# PowerInput_Switch.net
KiCad netlist of a schematic drawn in Altium Designer
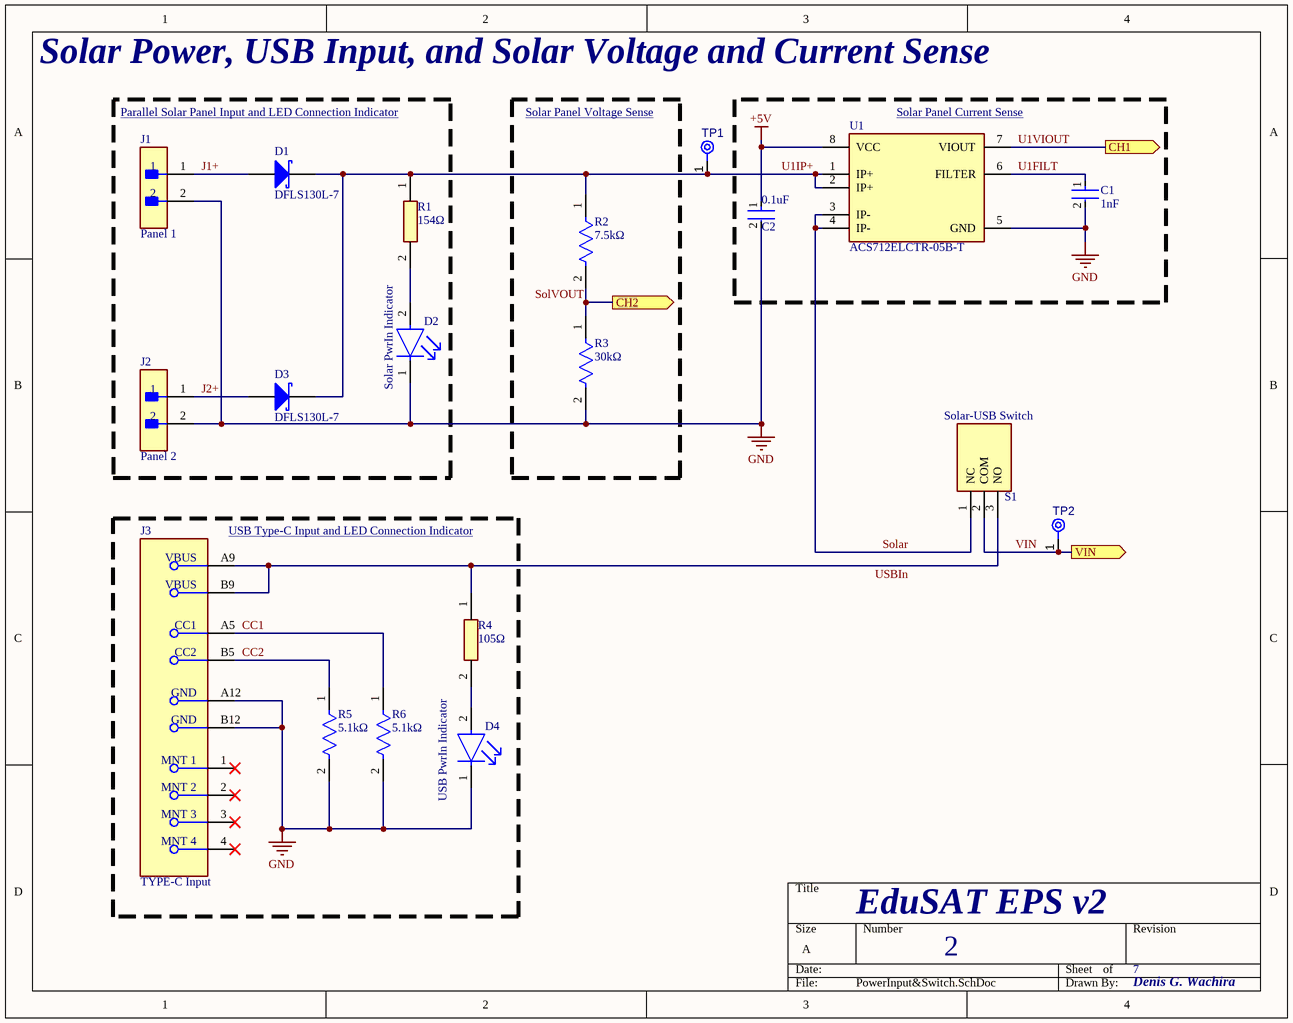
[diagram p0: PowerInput&Switch.SchDoc]

(export (version "E")
  (design (tool "Eeschema 10.0.6"))
  (components
    (comp (ref "C1")
      (value "1nF")
      (footprint "FP-CL21-IPC_B")
      (fields (field (name "TOLERANCE") "10%") (field (name "VOLTAGE") "50V"))
      (libsource (lib "Altium Content Vault") (part "b4654b650e69147ec39a6b967a45e02"))
    )
    (comp (ref "C2")
      (value "0.1uF")
      (footprint "FP-CL21-IPC_A")
      (description "50V 0.1uF X7R ±10% 0805 Multilayer Ceramic Capacitors MLCC - SMD/SMT ROHS TCC0805X7R104K500DT")
      (fields (field (name "TOLERANCE") "10%"))
      (libsource (lib "Altium Content Vault") (part "b4654b650e69147ec39a6b967a45e02"))
    )
    (comp (ref "D1")
      (value "DFLS130L-7")
      (footprint "DIOD-POWERDI123-2_A_V")
      (description "Schottky Barrier Rectifier, 30 V, 1 A, -40 to 125 degC, 2-Pin SMD, RoHS, Tape and Reel")
      (fields (field (name "MANUFACTURER") "Diodes Inc"))
      (libsource (lib "Altium Content Vault") (part "DSKY-AK-2"))
    )
    (comp (ref "D2")
      (value "Solar PwrIn Indicator")
      (footprint "FP-LTST-C170GKT-MFG")
      (description "LED GREEN CLEAR SMD KT-0805G")
      (fields (field (name "VOLTAGE") "5V"))
      (libsource (lib "Altium Content Vault") (part "8706943c75ba83719d021d2fdc84c58"))
    )
    (comp (ref "D3")
      (value "DFLS130L-7")
      (footprint "DIOD-POWERDI123-2_A_V")
      (description "Schottky Barrier Rectifier, 30 V, 1 A, -40 to 125 degC, 2-Pin SMD, RoHS, Tape and Reel")
      (fields (field (name "MANUFACTURER") "Diodes Inc"))
      (libsource (lib "Altium Content Vault") (part "DSKY-AK-2"))
    )
    (comp (ref "D4")
      (value "USB PwrIn Indicator")
      (footprint "FP-LTST-C170GKT-MFG")
      (description "LED GREEN CLEAR SMD KT-0805G")
      (fields (field (name "VOLTAGE") "5V"))
      (libsource (lib "Altium Content Vault") (part "8706943c75ba83719d021d2fdc84c58"))
    )
    (comp (ref "J1")
      (value "Panel 1")
      (footprint "FP-S2B-XH-A-1_LF_SN-MFG")
      (description "CONN HEADER R/A 2POS 2.5MM HCZZ0139-2")
      (libsource (lib "Altium Content Vault") (part "3bc925449376181038e59eaffc5286c"))
    )
    (comp (ref "J2")
      (value "Panel 2")
      (footprint "FP-S2B-XH-A-1_LF_SN-MFG")
      (description "CONN HEADER R/A 2POS 2.5MM HCZZ0139-2")
      (libsource (lib "Altium Content Vault") (part "3bc925449376181038e59eaffc5286c"))
    )
    (comp (ref "J3")
      (value "TYPE-C Input")
      (footprint "FP-USB4125-GF-A-0190-MFG")
      (description "3A 1 Surface Mount，Right Angle 6P Female -40℃~+85℃ Type-C SMD USB Connectors ROHS")
      (libsource (lib "University of Nairobi") (part "a055484d46e58b234844902c9fd883a"))
    )
    (comp (ref "R1")
      (value "154Ω")
      (footprint "SamacSys:RESC2012X65N")
      (fields (field (name "MANUFACTURER_PART_NUMBER") "AECR0805F27R0K9"))
      (libsource (lib "*") (part "AECR0805F27R0K9"))
    )
    (comp (ref "R2")
      (value "7.5kΩ")
      (footprint "FP-MCR10-IPC_A")
      (description "Thick Film Chip Resistor, 0805, 7.5kΩ, 1%, 100ppm/°C, 0.125W, 150V 0805W8F7501T5E")
      (fields (field (name "TOLERANCE") "1%"))
      (libsource (lib "Altium Content Vault") (part "1029c3af85768c4190bb7ad29bc67b5"))
    )
    (comp (ref "R3")
      (value "30kΩ")
      (footprint "FP-MCR10-IPC_A")
      (description "Thick Film Chip Resistor, 0805, 30kΩ, 1%, 100ppm/°C, 0.125W, 150V 0805W8F7501T5E")
      (fields (field (name "TOLERANCE") "1%"))
      (libsource (lib "Altium Content Vault") (part "1029c3af85768c4190bb7ad29bc67b5"))
    )
    (comp (ref "R4")
      (value "105Ω")
      (footprint "SamacSys:RESC2012X65N")
      (fields (field (name "MANUFACTURER_PART_NUMBER") "AECR0805F27R0K9"))
      (libsource (lib "*") (part "AECR0805F27R0K9"))
    )
    (comp (ref "R5")
      (value "5.1kΩ")
      (footprint "FP-MCR10-IPC_A")
      (description "Thick Film Chip Resistor, 0805, 5.1kΩ, 1%, 100ppm/°C, 0.125W, 150V 0805W8F5101T5E")
      (fields (field (name "TOLERANCE") "1%"))
      (libsource (lib "Altium Content Vault") (part "1029c3af85768c4190bb7ad29bc67b5"))
    )
    (comp (ref "R6")
      (value "5.1kΩ")
      (footprint "FP-MCR10-IPC_A")
      (description "Thick Film Chip Resistor, 0805, 5.1kΩ, 1%, 100ppm/°C, 0.125W, 150V 0805W8F5101T5E")
      (fields (field (name "TOLERANCE") "1%"))
      (libsource (lib "Altium Content Vault") (part "1029c3af85768c4190bb7ad29bc67b5"))
    )
    (comp (ref "S1")
      (value "Solar-USB Switch")
      (footprint "SamacSys:SS12D10L3")
      (description "Switch")
      (fields (field (name "MANUFACTURER_PART_NUMBER") "SS-12D10L3"))
      (libsource (lib "*") (part "SS-12D10L3"))
    )
    (comp (ref "TP1")
      (value "TPAD6R")
      (footprint "TP06R")
      (description "0.6mm round")
      (libsource (lib "University of Nairobi") (part "CMP-001-0001-4"))
    )
    (comp (ref "TP2")
      (value "TPAD6R")
      (footprint "TP06R")
      (description "0.6mm round")
      (libsource (lib "University of Nairobi") (part "CMP-001-0001-4"))
    )
    (comp (ref "U1")
      (value "ACS712ELCTR-05B-T")
      (footprint "FP-LC-8-IPC_A")
      (description "SENSOR CURRENT HALL 5A AC/DC")
      (fields (field (name "VOLTAGE") "5V"))
      (libsource (lib "Altium Content Vault") (part "160a4736de78720bdb7fdad13a6f0ac"))
    )
  )
  (nets
    (net (code "1") (name "+5V") (class "Default")
      (node (ref "C2") (pin "1") (pinfunction "1_1") (pintype "passive"))
      (node (ref "U1") (pin "8") (pinfunction "VCC_8") (pintype "power_in"))
    )
    (net (code "2") (name "/CC1") (class "Default")
      (node (ref "J3") (pin "A5") (pinfunction "CC1_A5") (pintype "passive"))
      (node (ref "R6") (pin "1") (pinfunction "1_1") (pintype "passive"))
    )
    (net (code "3") (name "/CC2") (class "Default")
      (node (ref "J3") (pin "B5") (pinfunction "CC2_B5") (pintype "passive"))
      (node (ref "R5") (pin "1") (pinfunction "1_1") (pintype "passive"))
    )
    (net (code "4") (name "/J1+") (class "Default")
      (node (ref "D1") (pin "1") (pinfunction "A_1") (pintype "passive"))
      (node (ref "J1") (pin "1") (pinfunction "1_1") (pintype "passive"))
    )
    (net (code "5") (name "/J2+") (class "Default")
      (node (ref "D3") (pin "1") (pinfunction "A_1") (pintype "passive"))
      (node (ref "J2") (pin "1") (pinfunction "1_1") (pintype "passive"))
    )
    (net (code "6") (name "/SolVOUT") (class "Default")
      (node (ref "R2") (pin "2") (pinfunction "2_2") (pintype "passive"))
      (node (ref "R3") (pin "1") (pinfunction "1_1") (pintype "passive"))
    )
    (net (code "7") (name "/Solar") (class "Default")
      (node (ref "S1") (pin "1") (pinfunction "NC_1") (pintype "passive"))
      (node (ref "U1") (pin "3") (pinfunction "IP-_3") (pintype "passive"))
      (node (ref "U1") (pin "4") (pinfunction "IP-_4") (pintype "passive"))
    )
    (net (code "8") (name "/U1FILT") (class "Default")
      (node (ref "C1") (pin "1") (pinfunction "1_1") (pintype "passive"))
      (node (ref "U1") (pin "6") (pinfunction "FILTER_6") (pintype "passive"))
    )
    (net (code "9") (name "/U1IP+") (class "Default")
      (node (ref "D1") (pin "2") (pinfunction "K_2") (pintype "passive"))
      (node (ref "D3") (pin "2") (pinfunction "K_2") (pintype "passive"))
      (node (ref "R1") (pin "1") (pinfunction "1_1") (pintype "passive"))
      (node (ref "R2") (pin "1") (pinfunction "1_1") (pintype "passive"))
      (node (ref "TP1") (pin "1") (pinfunction "TP_1") (pintype "passive"))
      (node (ref "U1") (pin "1") (pinfunction "IP+_1") (pintype "passive"))
      (node (ref "U1") (pin "2") (pinfunction "IP+_2") (pintype "passive"))
    )
    (net (code "10") (name "/U1VIOUT") (class "Default")
      (node (ref "U1") (pin "7") (pinfunction "VIOUT_7") (pintype "passive"))
    )
    (net (code "11") (name "/USBIn") (class "Default")
      (node (ref "J3") (pin "A9") (pinfunction "VBUS_A9") (pintype "passive"))
      (node (ref "J3") (pin "B9") (pinfunction "VBUS_B9") (pintype "passive"))
      (node (ref "R4") (pin "1") (pinfunction "1_1") (pintype "passive"))
      (node (ref "S1") (pin "3") (pinfunction "NO_3") (pintype "passive"))
    )
    (net (code "12") (name "/VIN") (class "Default")
      (node (ref "S1") (pin "2") (pinfunction "COM_2") (pintype "passive"))
      (node (ref "TP2") (pin "1") (pinfunction "TP_1") (pintype "passive"))
    )
    (net (code "13") (name "GND") (class "Default")
      (node (ref "C1") (pin "2") (pinfunction "2_2") (pintype "passive"))
      (node (ref "C2") (pin "2") (pinfunction "2_2") (pintype "passive"))
      (node (ref "D2") (pin "1") (pinfunction "C_1") (pintype "passive"))
      (node (ref "D4") (pin "1") (pinfunction "C_1") (pintype "passive"))
      (node (ref "J1") (pin "2") (pinfunction "2_2") (pintype "passive"))
      (node (ref "J2") (pin "2") (pinfunction "2_2") (pintype "passive"))
      (node (ref "J3") (pin "A12") (pinfunction "GND_A12") (pintype "passive"))
      (node (ref "J3") (pin "B12") (pinfunction "GND_B12") (pintype "passive"))
      (node (ref "R3") (pin "2") (pinfunction "2_2") (pintype "passive"))
      (node (ref "R5") (pin "2") (pinfunction "2_2") (pintype "passive"))
      (node (ref "R6") (pin "2") (pinfunction "2_2") (pintype "passive"))
      (node (ref "U1") (pin "5") (pinfunction "GND_5") (pintype "power_in"))
    )
    (net (code "14") (name "Net-(D2-A)") (class "Default")
      (node (ref "D2") (pin "2") (pinfunction "A_2") (pintype "passive"))
      (node (ref "R1") (pin "2") (pinfunction "2_2") (pintype "passive"))
    )
    (net (code "15") (name "Net-(D4-A)") (class "Default")
      (node (ref "D4") (pin "2") (pinfunction "A_2") (pintype "passive"))
      (node (ref "R4") (pin "2") (pinfunction "2_2") (pintype "passive"))
    )
    (net (code "16") (name "unconnected-(J3-MNT_1-Pad1)") (class "Default")
      (node (ref "J3") (pin "1") (pinfunction "MNT_1_1") (pintype "passive+no_connect"))
    )
    (net (code "17") (name "unconnected-(J3-MNT_2-Pad2)") (class "Default")
      (node (ref "J3") (pin "2") (pinfunction "MNT_2_2") (pintype "passive+no_connect"))
    )
    (net (code "18") (name "unconnected-(J3-MNT_3-Pad3)") (class "Default")
      (node (ref "J3") (pin "3") (pinfunction "MNT_3_3") (pintype "passive+no_connect"))
    )
    (net (code "19") (name "unconnected-(J3-MNT_4-Pad4)") (class "Default")
      (node (ref "J3") (pin "4") (pinfunction "MNT_4_4") (pintype "passive+no_connect"))
    )
  )
)
